# generic_midi_1.net
KiCad netlist of a schematic drawn in EAGLE
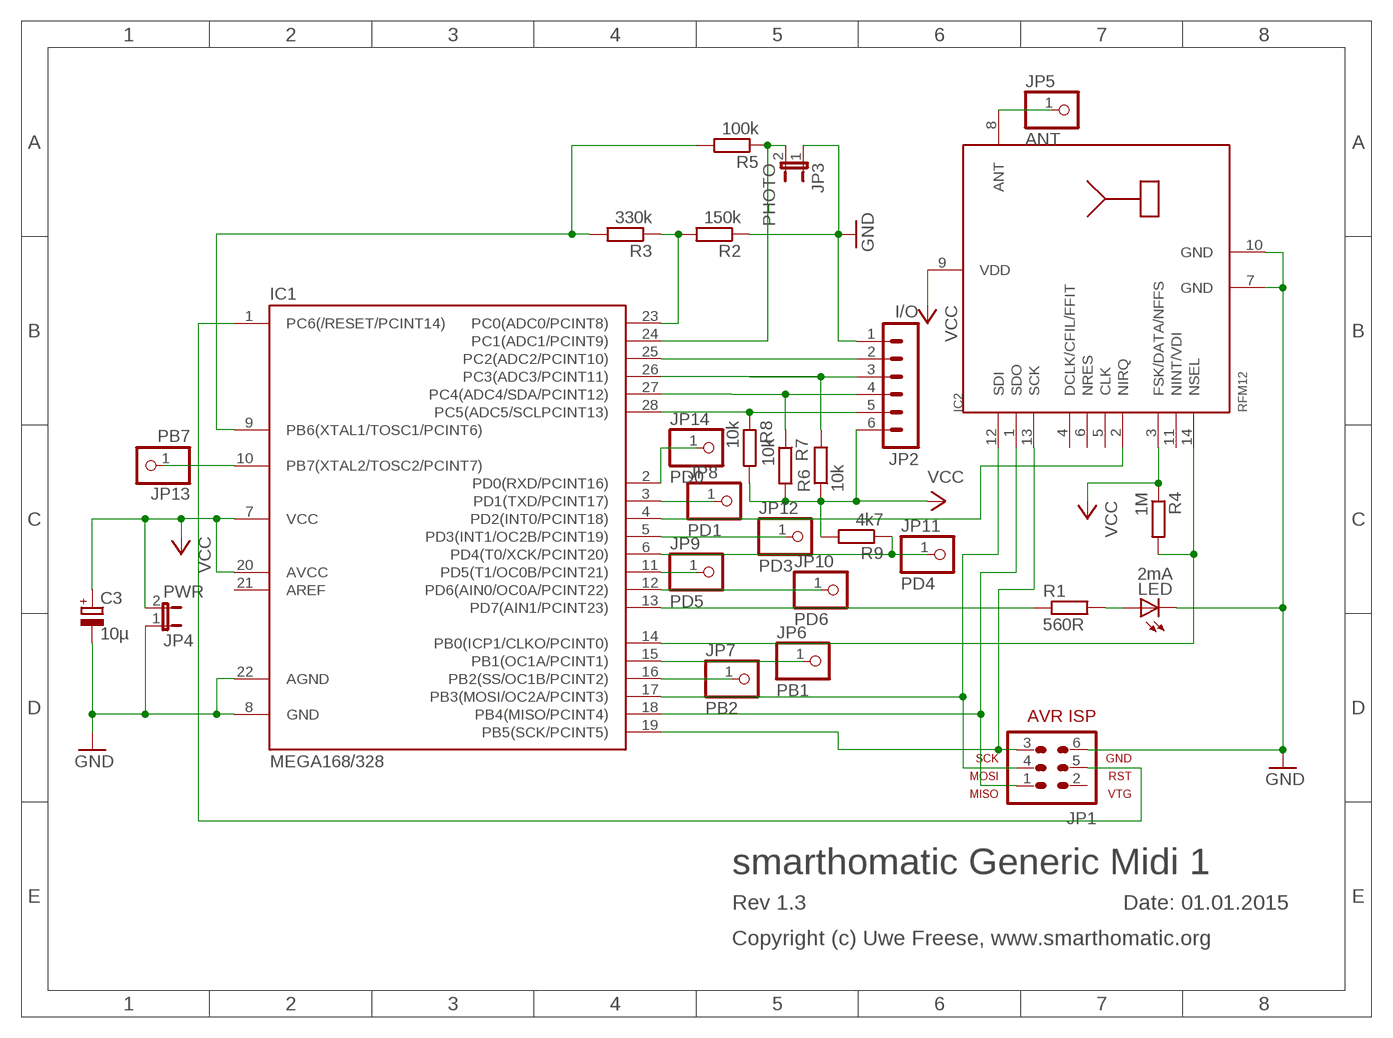
[diagram p0: schematic, sheet 1]

(export (version "E")
  (design (tool "Eeschema 10.0.6"))
  (components
    (comp (ref "C3")
      (value "10µ")
      (footprint "eagle-import:E1,8-4")
      (libsource (lib "eagle-import") (part "CPOL-EUE1.8-4"))
    )
    (comp (ref "IC1")
      (value "MEGA168/328")
      (footprint "eagle-import:DIL28-3")
      (libsource (lib "eagle-import") (part "MEGA48/88/168-PU"))
    )
    (comp (ref "IC2")
      (value "RFM12")
      (footprint "eagle-import:RFM")
      (libsource (lib "eagle-import") (part "RFM12"))
    )
    (comp (ref "JP1")
      (value "AVR-ISP-6")
      (footprint "eagle-import:AVR-ISP-6")
      (libsource (lib "eagle-import") (part "AVR-ISP-6"))
    )
    (comp (ref "JP2")
      (value "I/O")
      (footprint "eagle-import:MA06-1")
      (libsource (lib "eagle-import") (part "MA06-1"))
    )
    (comp (ref "JP3")
      (value "PHOTO")
      (footprint "eagle-import:JP1")
      (libsource (lib "eagle-import") (part "JP1E"))
    )
    (comp (ref "JP4")
      (value "PWR")
      (footprint "eagle-import:JP1")
      (libsource (lib "eagle-import") (part "JP1E"))
    )
    (comp (ref "JP5")
      (value "ANT")
      (footprint "eagle-import:1X01")
      (libsource (lib "eagle-import") (part "PINHD-1X1"))
    )
    (comp (ref "JP6")
      (value "PB1")
      (footprint "eagle-import:1X01")
      (libsource (lib "eagle-import") (part "PINHD-1X1"))
    )
    (comp (ref "JP7")
      (value "PB2")
      (footprint "eagle-import:1X01")
      (libsource (lib "eagle-import") (part "PINHD-1X1"))
    )
    (comp (ref "JP8")
      (value "PD1")
      (footprint "eagle-import:1X01")
      (libsource (lib "eagle-import") (part "PINHD-1X1"))
    )
    (comp (ref "JP9")
      (value "PD5")
      (footprint "eagle-import:1X01")
      (libsource (lib "eagle-import") (part "PINHD-1X1"))
    )
    (comp (ref "JP10")
      (value "PD6")
      (footprint "eagle-import:1X01")
      (libsource (lib "eagle-import") (part "PINHD-1X1"))
    )
    (comp (ref "JP11")
      (value "PD4")
      (footprint "eagle-import:1X01")
      (libsource (lib "eagle-import") (part "PINHD-1X1"))
    )
    (comp (ref "JP12")
      (value "PD3")
      (footprint "eagle-import:1X01")
      (libsource (lib "eagle-import") (part "PINHD-1X1"))
    )
    (comp (ref "JP13")
      (value "PB7")
      (footprint "eagle-import:1X01")
      (libsource (lib "eagle-import") (part "PINHD-1X1"))
    )
    (comp (ref "JP14")
      (value "PD0")
      (footprint "eagle-import:1X01")
      (libsource (lib "eagle-import") (part "PINHD-1X1"))
    )
    (comp (ref "LED")
      (value "2mA")
      (footprint "eagle-import:LED3MM")
      (libsource (lib "eagle-import") (part "LED3MM"))
    )
    (comp (ref "R1")
      (value "560R")
      (footprint "eagle-import:0207_7")
      (libsource (lib "eagle-import") (part "R-EU_0207/7"))
    )
    (comp (ref "R2")
      (value "150k")
      (footprint "eagle-import:0207_7")
      (libsource (lib "eagle-import") (part "R-EU_0207/7"))
    )
    (comp (ref "R3")
      (value "330k")
      (footprint "eagle-import:0207_7")
      (libsource (lib "eagle-import") (part "R-EU_0207/7"))
    )
    (comp (ref "R4")
      (value "1M")
      (footprint "eagle-import:0207_7")
      (libsource (lib "eagle-import") (part "R-EU_0207/7"))
    )
    (comp (ref "R5")
      (value "100k")
      (footprint "eagle-import:0207_7")
      (libsource (lib "eagle-import") (part "R-EU_0207/7"))
    )
    (comp (ref "R6")
      (value "10k")
      (footprint "eagle-import:0207_7")
      (libsource (lib "eagle-import") (part "R-EU_0207/7"))
    )
    (comp (ref "R7")
      (value "10k")
      (footprint "eagle-import:0207_7")
      (libsource (lib "eagle-import") (part "R-EU_0207/7"))
    )
    (comp (ref "R8")
      (value "10k")
      (footprint "eagle-import:0207_7")
      (libsource (lib "eagle-import") (part "R-EU_0207/7"))
    )
    (comp (ref "R9")
      (value "4k7")
      (footprint "eagle-import:0207_7")
      (libsource (lib "eagle-import") (part "R-EU_0207/7"))
    )
  )
  (nets
    (net (code "1") (name "GND") (class "Default")
      (node (ref "C3") (pin "-") (pinfunction "-_-") (pintype "passive"))
      (node (ref "IC1") (pin "22") (pinfunction "AGND_22") (pintype "power_in"))
      (node (ref "IC1") (pin "8") (pinfunction "GND_8") (pintype "power_in"))
      (node (ref "IC2") (pin "10") (pinfunction "GND_10") (pintype "power_in"))
      (node (ref "IC2") (pin "7") (pinfunction "GND_7") (pintype "power_in"))
      (node (ref "JP1") (pin "6") (pinfunction "6_6") (pintype "passive"))
      (node (ref "JP2") (pin "1") (pinfunction "1_1") (pintype "passive"))
      (node (ref "JP3") (pin "1") (pinfunction "1_1") (pintype "passive"))
      (node (ref "JP4") (pin "1") (pinfunction "1_1") (pintype "passive"))
      (node (ref "LED") (pin "K") (pinfunction "C_K") (pintype "passive"))
      (node (ref "R2") (pin "1") (pinfunction "1_1") (pintype "passive"))
    )
    (net (code "2") (name "Net-(IC1-PB0(ICP1{slash}CLKO{slash}PCINT0))") (class "Default")
      (node (ref "IC1") (pin "14") (pinfunction "PB0(ICP1/CLKO/PCINT0)_14") (pintype "bidirectional"))
      (node (ref "IC2") (pin "14") (pinfunction "NSEL_14") (pintype "bidirectional"))
      (node (ref "R4") (pin "2") (pinfunction "2_2") (pintype "passive"))
    )
    (net (code "3") (name "Net-(IC1-PB1(OC1A{slash}PCINT1))") (class "Default")
      (node (ref "IC1") (pin "15") (pinfunction "PB1(OC1A/PCINT1)_15") (pintype "bidirectional"))
      (node (ref "JP6") (pin "1") (pinfunction "1_1") (pintype "passive"))
    )
    (net (code "4") (name "Net-(IC1-PB2(SS{slash}OC1B{slash}PCINT2))") (class "Default")
      (node (ref "IC1") (pin "16") (pinfunction "PB2(SS/OC1B/PCINT2)_16") (pintype "bidirectional"))
      (node (ref "JP7") (pin "1") (pinfunction "1_1") (pintype "passive"))
    )
    (net (code "5") (name "Net-(IC1-PB3(MOSI{slash}OC2A{slash}PCINT3))") (class "Default")
      (node (ref "IC1") (pin "17") (pinfunction "PB3(MOSI/OC2A/PCINT3)_17") (pintype "bidirectional"))
      (node (ref "IC2") (pin "12") (pinfunction "SDI_12") (pintype "bidirectional"))
      (node (ref "JP1") (pin "4") (pinfunction "4_4") (pintype "passive"))
    )
    (net (code "6") (name "Net-(IC1-PB4(MISO{slash}PCINT4))") (class "Default")
      (node (ref "IC1") (pin "18") (pinfunction "PB4(MISO/PCINT4)_18") (pintype "bidirectional"))
      (node (ref "IC2") (pin "1") (pinfunction "SDO_1") (pintype "bidirectional"))
      (node (ref "JP1") (pin "1") (pinfunction "1_1") (pintype "passive"))
    )
    (net (code "7") (name "Net-(IC1-PB5(SCK{slash}PCINT5))") (class "Default")
      (node (ref "IC1") (pin "19") (pinfunction "PB5(SCK/PCINT5)_19") (pintype "bidirectional"))
      (node (ref "IC2") (pin "13") (pinfunction "SCK_13") (pintype "bidirectional"))
      (node (ref "JP1") (pin "3") (pinfunction "3_3") (pintype "passive"))
    )
    (net (code "8") (name "Net-(IC1-PB6(XTAL1{slash}TOSC1{slash}PCINT6))") (class "Default")
      (node (ref "IC1") (pin "9") (pinfunction "PB6(XTAL1/TOSC1/PCINT6)_9") (pintype "bidirectional"))
      (node (ref "R3") (pin "2") (pinfunction "2_2") (pintype "passive"))
      (node (ref "R5") (pin "2") (pinfunction "2_2") (pintype "passive"))
    )
    (net (code "9") (name "Net-(IC1-PB7(XTAL2{slash}TOSC2{slash}PCINT7))") (class "Default")
      (node (ref "IC1") (pin "10") (pinfunction "PB7(XTAL2/TOSC2/PCINT7)_10") (pintype "bidirectional"))
      (node (ref "JP13") (pin "1") (pinfunction "1_1") (pintype "passive"))
    )
    (net (code "10") (name "Net-(IC1-PC0(ADC0{slash}PCINT8))") (class "Default")
      (node (ref "IC1") (pin "23") (pinfunction "PC0(ADC0/PCINT8)_23") (pintype "bidirectional"))
      (node (ref "R2") (pin "2") (pinfunction "2_2") (pintype "passive"))
      (node (ref "R3") (pin "1") (pinfunction "1_1") (pintype "passive"))
    )
    (net (code "11") (name "Net-(IC1-PC1(ADC1{slash}PCINT9))") (class "Default")
      (node (ref "IC1") (pin "24") (pinfunction "PC1(ADC1/PCINT9)_24") (pintype "bidirectional"))
      (node (ref "JP3") (pin "2") (pinfunction "2_2") (pintype "passive"))
      (node (ref "R5") (pin "1") (pinfunction "1_1") (pintype "passive"))
    )
    (net (code "12") (name "Net-(IC1-PC2(ADC2{slash}PCINT10))") (class "Default")
      (node (ref "IC1") (pin "25") (pinfunction "PC2(ADC2/PCINT10)_25") (pintype "bidirectional"))
      (node (ref "JP2") (pin "2") (pinfunction "2_2") (pintype "passive"))
    )
    (net (code "13") (name "Net-(IC1-PC3(ADC3{slash}PCINT11))") (class "Default")
      (node (ref "IC1") (pin "26") (pinfunction "PC3(ADC3/PCINT11)_26") (pintype "bidirectional"))
      (node (ref "JP2") (pin "3") (pinfunction "3_3") (pintype "passive"))
      (node (ref "R6") (pin "2") (pinfunction "2_2") (pintype "passive"))
    )
    (net (code "14") (name "Net-(IC1-PC4(ADC4{slash}SDA{slash}PCINT12))") (class "Default")
      (node (ref "IC1") (pin "27") (pinfunction "PC4(ADC4/SDA/PCINT12)_27") (pintype "bidirectional"))
      (node (ref "JP2") (pin "4") (pinfunction "4_4") (pintype "passive"))
      (node (ref "R7") (pin "1") (pinfunction "1_1") (pintype "passive"))
    )
    (net (code "15") (name "Net-(IC1-PC5(ADC5{slash}SCLPCINT13))") (class "Default")
      (node (ref "IC1") (pin "28") (pinfunction "PC5(ADC5/SCLPCINT13)_28") (pintype "bidirectional"))
      (node (ref "JP2") (pin "5") (pinfunction "5_5") (pintype "passive"))
      (node (ref "R8") (pin "1") (pinfunction "1_1") (pintype "passive"))
    )
    (net (code "16") (name "Net-(IC1-PC6({slash}RESET{slash}PCINT14))") (class "Default")
      (node (ref "IC1") (pin "1") (pinfunction "PC6(/RESET/PCINT14)_1") (pintype "bidirectional"))
      (node (ref "JP1") (pin "5") (pinfunction "5_5") (pintype "passive"))
    )
    (net (code "17") (name "Net-(IC1-PD0(RXD{slash}PCINT16))") (class "Default")
      (node (ref "IC1") (pin "2") (pinfunction "PD0(RXD/PCINT16)_2") (pintype "bidirectional"))
      (node (ref "JP14") (pin "1") (pinfunction "1_1") (pintype "passive"))
    )
    (net (code "18") (name "Net-(IC1-PD1(TXD{slash}PCINT17))") (class "Default")
      (node (ref "IC1") (pin "3") (pinfunction "PD1(TXD/PCINT17)_3") (pintype "bidirectional"))
      (node (ref "JP8") (pin "1") (pinfunction "1_1") (pintype "passive"))
    )
    (net (code "19") (name "Net-(IC1-PD2(INT0{slash}PCINT18))") (class "Default")
      (node (ref "IC1") (pin "4") (pinfunction "PD2(INT0/PCINT18)_4") (pintype "bidirectional"))
      (node (ref "IC2") (pin "2") (pinfunction "NIRQ_2") (pintype "bidirectional"))
    )
    (net (code "20") (name "Net-(IC1-PD3(INT1{slash}OC2B{slash}PCINT19))") (class "Default")
      (node (ref "IC1") (pin "5") (pinfunction "PD3(INT1/OC2B/PCINT19)_5") (pintype "bidirectional"))
      (node (ref "JP12") (pin "1") (pinfunction "1_1") (pintype "passive"))
    )
    (net (code "21") (name "Net-(IC1-PD4(T0{slash}XCK{slash}PCINT20))") (class "Default")
      (node (ref "IC1") (pin "6") (pinfunction "PD4(T0/XCK/PCINT20)_6") (pintype "bidirectional"))
      (node (ref "JP11") (pin "1") (pinfunction "1_1") (pintype "passive"))
      (node (ref "R9") (pin "1") (pinfunction "1_1") (pintype "passive"))
    )
    (net (code "22") (name "Net-(IC1-PD5(T1{slash}OC0B{slash}PCINT21))") (class "Default")
      (node (ref "IC1") (pin "11") (pinfunction "PD5(T1/OC0B/PCINT21)_11") (pintype "bidirectional"))
      (node (ref "JP9") (pin "1") (pinfunction "1_1") (pintype "passive"))
    )
    (net (code "23") (name "Net-(IC1-PD6(AIN0{slash}OC0A{slash}PCINT22))") (class "Default")
      (node (ref "IC1") (pin "12") (pinfunction "PD6(AIN0/OC0A/PCINT22)_12") (pintype "bidirectional"))
      (node (ref "JP10") (pin "1") (pinfunction "1_1") (pintype "passive"))
    )
    (net (code "24") (name "Net-(IC1-PD7(AIN1{slash}PCINT23))") (class "Default")
      (node (ref "IC1") (pin "13") (pinfunction "PD7(AIN1/PCINT23)_13") (pintype "bidirectional"))
      (node (ref "R1") (pin "1") (pinfunction "1_1") (pintype "passive"))
    )
    (net (code "25") (name "Net-(IC2-ANT)") (class "Default")
      (node (ref "IC2") (pin "8") (pinfunction "ANT_8") (pintype "output"))
      (node (ref "JP5") (pin "1") (pinfunction "1_1") (pintype "passive"))
    )
    (net (code "26") (name "Net-(LED-PadA)") (class "Default")
      (node (ref "LED") (pin "A") (pinfunction "A_A") (pintype "passive"))
      (node (ref "R1") (pin "2") (pinfunction "2_2") (pintype "passive"))
    )
    (net (code "27") (name "VCC") (class "Default")
      (node (ref "C3") (pin "+") (pinfunction "+_+") (pintype "passive"))
      (node (ref "IC1") (pin "20") (pinfunction "AVCC_20") (pintype "passive"))
      (node (ref "IC1") (pin "7") (pinfunction "VCC_7") (pintype "power_in"))
      (node (ref "IC2") (pin "3") (pinfunction "FSK/DATA/NFFS_3") (pintype "bidirectional"))
      (node (ref "IC2") (pin "9") (pinfunction "VDD_9") (pintype "power_in"))
      (node (ref "JP2") (pin "6") (pinfunction "6_6") (pintype "passive"))
      (node (ref "JP4") (pin "2") (pinfunction "2_2") (pintype "passive"))
      (node (ref "R4") (pin "1") (pinfunction "1_1") (pintype "passive"))
      (node (ref "R6") (pin "1") (pinfunction "1_1") (pintype "passive"))
      (node (ref "R7") (pin "2") (pinfunction "2_2") (pintype "passive"))
      (node (ref "R8") (pin "2") (pinfunction "2_2") (pintype "passive"))
      (node (ref "R9") (pin "2") (pinfunction "2_2") (pintype "passive"))
    )
    (net (code "28") (name "unconnected-(IC1-AREF-Pad21)") (class "Default")
      (node (ref "IC1") (pin "21") (pinfunction "AREF_21") (pintype "passive"))
    )
    (net (code "29") (name "unconnected-(IC2-CLK-Pad5)") (class "Default")
      (node (ref "IC2") (pin "5") (pinfunction "CLK_5") (pintype "bidirectional"))
    )
    (net (code "30") (name "unconnected-(IC2-DCLK{slash}CFIL{slash}FFIT-Pad4)") (class "Default")
      (node (ref "IC2") (pin "4") (pinfunction "DCLK/CFIL/FFIT_4") (pintype "bidirectional"))
    )
    (net (code "31") (name "unconnected-(IC2-NINT{slash}VDI-Pad11)") (class "Default")
      (node (ref "IC2") (pin "11") (pinfunction "NINT/VDI_11") (pintype "bidirectional"))
    )
    (net (code "32") (name "unconnected-(IC2-NRES-Pad6)") (class "Default")
      (node (ref "IC2") (pin "6") (pinfunction "NRES_6") (pintype "bidirectional"))
    )
    (net (code "33") (name "unconnected-(JP1-Pad2)") (class "Default")
      (node (ref "JP1") (pin "2") (pinfunction "2_2") (pintype "passive"))
    )
  )
)
